# Power_Supply.net
KiCad netlist of a schematic drawn in Altium Designer
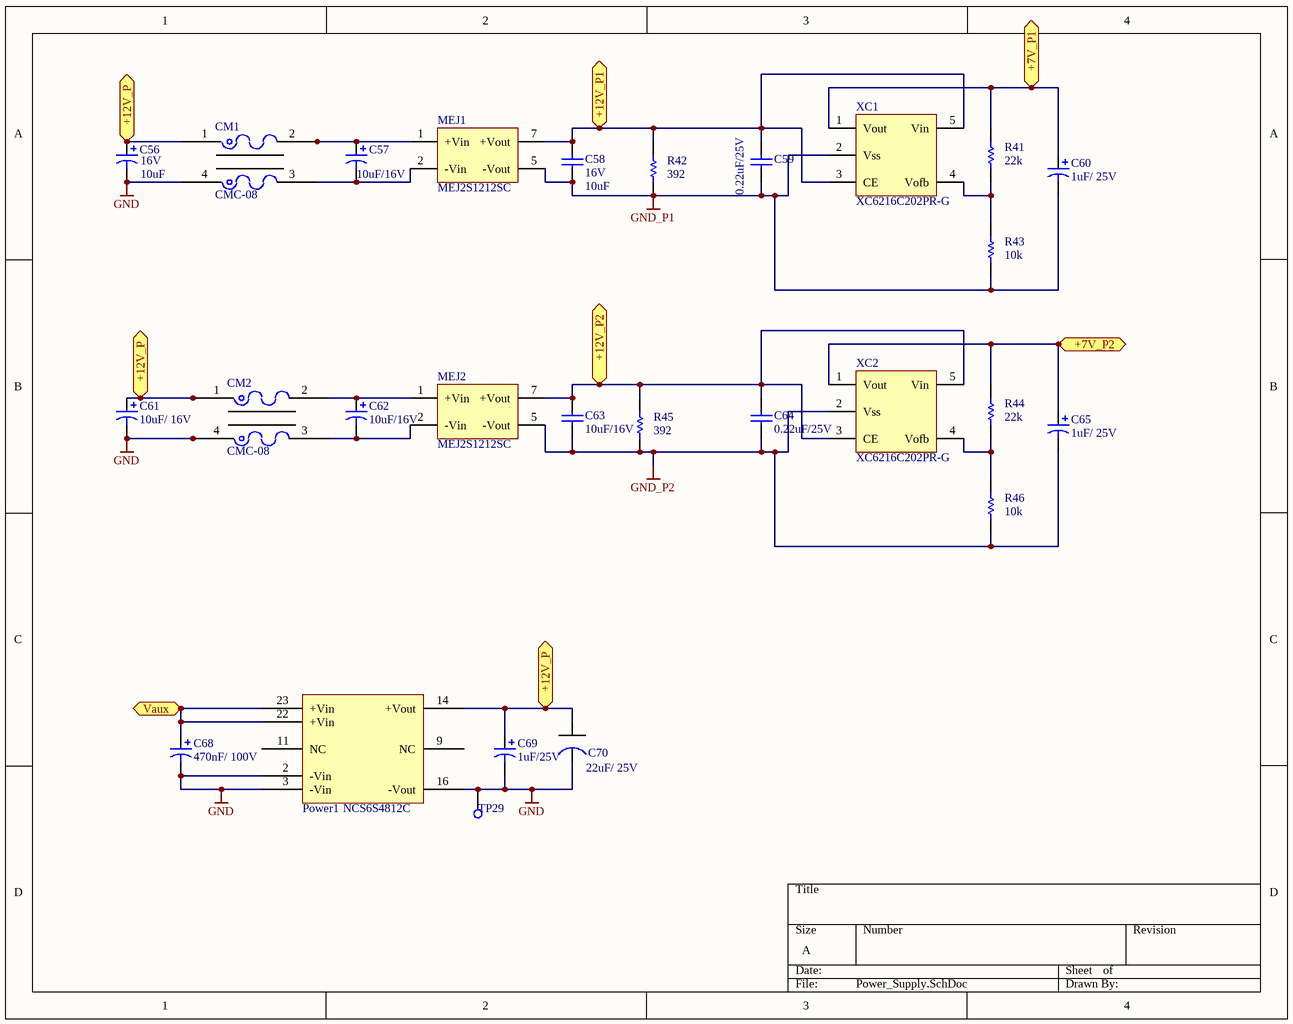
[diagram p0: Power_Supply.SchDoc]

(export (version "E")
  (design (tool "Eeschema 10.0.6"))
  (components
    (comp (ref "C56")
      (value "16V")
      (footprint "1812")
      (description "Polarized Capacitor (Surface Mount)")
      (fields (field (name "ALTIUM_VALUE") "10uF") (field (name "PUBLISHER") "Altium Limited"))
      (libsource (lib "Miscellaneous Devices") (part "Cap Pol3"))
    )
    (comp (ref "C57")
      (value "10uF/16V")
      (footprint "1812")
      (description "Polarized Capacitor (Surface Mount)")
      (fields (field (name "Comment") "Cap Pol3") (field (name "PUBLISHER") "Altium Limited"))
      (libsource (lib "Miscellaneous Devices") (part "Cap Pol3"))
    )
    (comp (ref "C58")
      (value "16V")
      (footprint "C1206")
      (description "Capacitor (Semiconductor SIM Model)")
      (fields (field (name "ALTIUM_VALUE") "10uF") (field (name "PUBLISHER") "Altium Limited"))
      (libsource (lib "Miscellaneous Devices") (part "Cap Semi"))
    )
    (comp (ref "C59")
      (value "0.22uF/25V")
      (footprint "C1206")
      (description "Capacitor (Semiconductor SIM Model)")
      (fields (field (name "Comment") "Cap Semi") (field (name "PUBLISHER") "Altium Limited"))
      (libsource (lib "Miscellaneous Devices") (part "Cap Semi"))
    )
    (comp (ref "C60")
      (value "1uF/ 25V")
      (footprint "C0805")
      (description "Polarized Capacitor (Surface Mount)")
      (fields (field (name "Comment") "Cap Pol3") (field (name "PUBLISHER") "Altium Limited"))
      (libsource (lib "Miscellaneous Devices") (part "Cap Pol3"))
    )
    (comp (ref "C61")
      (value "10uF/ 16V")
      (footprint "1812")
      (description "Polarized Capacitor (Surface Mount)")
      (fields (field (name "Comment") "Cap Pol3") (field (name "PUBLISHER") "Altium Limited"))
      (libsource (lib "Miscellaneous Devices") (part "Cap Pol3"))
    )
    (comp (ref "C62")
      (value "10uF/16V")
      (footprint "1812")
      (description "Polarized Capacitor (Surface Mount)")
      (fields (field (name "Comment") "Cap Pol3") (field (name "PUBLISHER") "Altium Limited"))
      (libsource (lib "Miscellaneous Devices") (part "Cap Pol3"))
    )
    (comp (ref "C63")
      (value "10uF/16V")
      (footprint "C1206")
      (description "Capacitor (Semiconductor SIM Model)")
      (fields (field (name "Comment") "Cap Semi") (field (name "PUBLISHER") "Altium Limited"))
      (libsource (lib "Miscellaneous Devices") (part "Cap Semi"))
    )
    (comp (ref "C64")
      (value "0.22uF/25V")
      (footprint "C1206")
      (description "Capacitor (Semiconductor SIM Model)")
      (fields (field (name "Comment") "Cap Semi") (field (name "PUBLISHER") "Altium Limited"))
      (libsource (lib "Miscellaneous Devices") (part "Cap Semi"))
    )
    (comp (ref "C65")
      (value "1uF/ 25V")
      (footprint "C0805")
      (description "Polarized Capacitor (Surface Mount)")
      (fields (field (name "Comment") "Cap Pol3") (field (name "PUBLISHER") "Altium Limited"))
      (libsource (lib "Miscellaneous Devices") (part "Cap Pol3"))
    )
    (comp (ref "C68")
      (value "470nF/ 100V")
      (footprint "C0805")
      (description "Polarized Capacitor (Surface Mount)")
      (fields (field (name "Comment") "Cap Pol3") (field (name "PUBLISHER") "Altium Limited"))
      (libsource (lib "Miscellaneous Devices") (part "Cap Pol3"))
    )
    (comp (ref "C69")
      (value "1uF/25V")
      (footprint "C0805")
      (description "Polarized Capacitor (Surface Mount)")
      (fields (field (name "Comment") "Cap Pol3") (field (name "PUBLISHER") "Altium Limited"))
      (libsource (lib "Miscellaneous Devices") (part "Cap Pol3"))
    )
    (comp (ref "C70")
      (value "22uF")
      (footprint "Cap_tantalum")
      (fields (field (name "ALTIUM_UNNAMED_1") "22uF/ 25V"))
      (libsource (lib "Schlib1") (part "Cap_tantalum"))
    )
    (comp (ref "CM1")
      (value "CMC-08")
      (footprint "CMC-08")
      (description "Common mode choke")
      (libsource (lib "lib_ankit") (part "CMC-08"))
    )
    (comp (ref "CM2")
      (value "CMC-08")
      (footprint "CMC-08")
      (description "Common mode choke")
      (libsource (lib "lib_ankit") (part "CMC-08"))
    )
    (comp (ref "MEJ1")
      (value "MEJ2S1212SC")
      (footprint "MEJ2")
      (libsource (lib "Gan_cuk converter") (part "Power supply2"))
    )
    (comp (ref "MEJ2")
      (value "MEJ2S1212SC")
      (footprint "MEJ2")
      (libsource (lib "Gan_cuk converter") (part "Power supply2"))
    )
    (comp (ref "Power1")
      (value "NCS6S4812C")
      (footprint "Power_main")
      (libsource (lib "Schlib1") (part "Power_main"))
    )
    (comp (ref "R41")
      (value "res_smd")
      (footprint "res_smd")
      (description "smd_res")
      (fields (field (name "ALTIUM_UNNAMED_1") "22k"))
      (libsource (lib "Schlib1") (part "res_smd"))
    )
    (comp (ref "R42")
      (value "res_smd")
      (footprint "res_smd")
      (description "smd_res")
      (fields (field (name "ALTIUM_UNNAMED_1") "392"))
      (libsource (lib "Schlib1") (part "res_smd"))
    )
    (comp (ref "R43")
      (value "res_smd")
      (footprint "res_smd")
      (description "smd_res")
      (fields (field (name "ALTIUM_UNNAMED_1") "10k"))
      (libsource (lib "Schlib1") (part "res_smd"))
    )
    (comp (ref "R44")
      (value "res_smd")
      (footprint "res_smd")
      (description "smd_res")
      (fields (field (name "ALTIUM_UNNAMED_1") "22k"))
      (libsource (lib "Schlib1") (part "res_smd"))
    )
    (comp (ref "R45")
      (value "res_smd")
      (footprint "res_smd")
      (description "smd_res")
      (fields (field (name "ALTIUM_UNNAMED_1") "392"))
      (libsource (lib "Schlib1") (part "res_smd"))
    )
    (comp (ref "R46")
      (value "res_smd")
      (footprint "res_smd")
      (description "smd_res")
      (fields (field (name "ALTIUM_UNNAMED_1") "10k"))
      (libsource (lib "Schlib1") (part "res_smd"))
    )
    (comp (ref "TP29")
      (value "Test Point")
      (footprint "Test Point")
      (libsource (lib "Gan_cuk converter") (part "Test Point"))
    )
    (comp (ref "XC1")
      (value "XC6216C202PR-G")
      (footprint "SOT-89-5")
      (libsource (lib "Gan_cuk converter") (part "power supply"))
    )
    (comp (ref "XC2")
      (value "XC6216C202PR-G")
      (footprint "SOT-89-5")
      (libsource (lib "Gan_cuk converter") (part "power supply"))
    )
  )
  (nets
    (net (code "1") (name "/+7V_P1") (class "Default")
      (node (ref "C60") (pin "1") (pinfunction "1_1") (pintype "passive"))
      (node (ref "R41") (pin "1") (pintype "passive"))
      (node (ref "XC1") (pin "1") (pinfunction "Vout_1") (pintype "passive"))
    )
    (net (code "2") (name "/+7V_P2") (class "Default")
      (node (ref "C65") (pin "1") (pinfunction "1_1") (pintype "passive"))
      (node (ref "R44") (pin "1") (pintype "passive"))
      (node (ref "XC2") (pin "1") (pinfunction "Vout_1") (pintype "passive"))
    )
    (net (code "3") (name "/+12V_P") (class "Default")
      (node (ref "C56") (pin "1") (pinfunction "1_1") (pintype "passive"))
      (node (ref "C61") (pin "1") (pinfunction "1_1") (pintype "passive"))
      (node (ref "C69") (pin "1") (pinfunction "1_1") (pintype "passive"))
      (node (ref "C70") (pin "1") (pintype "passive"))
      (node (ref "CM1") (pin "1") (pinfunction "1_1") (pintype "passive"))
      (node (ref "CM2") (pin "1") (pinfunction "1_1") (pintype "passive"))
      (node (ref "Power1") (pin "14") (pinfunction "+Vout_14") (pintype "passive"))
    )
    (net (code "4") (name "/+12V_P1") (class "Default")
      (node (ref "C58") (pin "2") (pinfunction "2_2") (pintype "passive"))
      (node (ref "C59") (pin "2") (pinfunction "2_2") (pintype "passive"))
      (node (ref "MEJ1") (pin "7") (pinfunction "+Vout_7") (pintype "passive"))
      (node (ref "R42") (pin "1") (pintype "passive"))
      (node (ref "XC1") (pin "3") (pinfunction "CE_3") (pintype "passive"))
      (node (ref "XC1") (pin "5") (pinfunction "Vin_5") (pintype "passive"))
    )
    (net (code "5") (name "/+12V_P2") (class "Default")
      (node (ref "C63") (pin "2") (pinfunction "2_2") (pintype "passive"))
      (node (ref "C64") (pin "2") (pinfunction "2_2") (pintype "passive"))
      (node (ref "MEJ2") (pin "7") (pinfunction "+Vout_7") (pintype "passive"))
      (node (ref "R45") (pin "1") (pintype "passive"))
      (node (ref "XC2") (pin "3") (pinfunction "CE_3") (pintype "passive"))
      (node (ref "XC2") (pin "5") (pinfunction "Vin_5") (pintype "passive"))
    )
    (net (code "6") (name "/Vaux") (class "Default")
      (node (ref "C68") (pin "1") (pinfunction "1_1") (pintype "passive"))
      (node (ref "Power1") (pin "22") (pinfunction "+Vin_22") (pintype "passive"))
      (node (ref "Power1") (pin "23") (pinfunction "+Vin_23") (pintype "passive"))
    )
    (net (code "7") (name "GND") (class "Default")
      (node (ref "C56") (pin "2") (pinfunction "2_2") (pintype "passive"))
      (node (ref "C61") (pin "2") (pinfunction "2_2") (pintype "passive"))
      (node (ref "C68") (pin "2") (pinfunction "2_2") (pintype "passive"))
      (node (ref "C69") (pin "2") (pinfunction "2_2") (pintype "passive"))
      (node (ref "C70") (pin "2") (pintype "passive"))
      (node (ref "CM1") (pin "4") (pinfunction "4_4") (pintype "passive"))
      (node (ref "CM2") (pin "4") (pinfunction "4_4") (pintype "passive"))
      (node (ref "Power1") (pin "16") (pinfunction "-Vout_16") (pintype "passive"))
      (node (ref "Power1") (pin "2") (pinfunction "-Vin_2") (pintype "passive"))
      (node (ref "Power1") (pin "3") (pinfunction "-Vin_3") (pintype "passive"))
      (node (ref "TP29") (pin "1") (pinfunction "TP?_1") (pintype "passive"))
    )
    (net (code "8") (name "GND_P1") (class "Default")
      (node (ref "C58") (pin "1") (pinfunction "1_1") (pintype "passive"))
      (node (ref "C59") (pin "1") (pinfunction "1_1") (pintype "passive"))
      (node (ref "C60") (pin "2") (pinfunction "2_2") (pintype "passive"))
      (node (ref "MEJ1") (pin "5") (pinfunction "-Vout_5") (pintype "passive"))
      (node (ref "R42") (pin "2") (pintype "passive"))
      (node (ref "R43") (pin "2") (pintype "passive"))
      (node (ref "XC1") (pin "2") (pinfunction "Vss_2") (pintype "passive"))
    )
    (net (code "9") (name "GND_P2") (class "Default")
      (node (ref "C63") (pin "1") (pinfunction "1_1") (pintype "passive"))
      (node (ref "C64") (pin "1") (pinfunction "1_1") (pintype "passive"))
      (node (ref "C65") (pin "2") (pinfunction "2_2") (pintype "passive"))
      (node (ref "MEJ2") (pin "5") (pinfunction "-Vout_5") (pintype "passive"))
      (node (ref "R45") (pin "2") (pintype "passive"))
      (node (ref "R46") (pin "2") (pintype "passive"))
      (node (ref "XC2") (pin "2") (pinfunction "Vss_2") (pintype "passive"))
    )
    (net (code "10") (name "Net-(MEJ1-+Vin)") (class "Default")
      (node (ref "C57") (pin "1") (pinfunction "1_1") (pintype "passive"))
      (node (ref "CM1") (pin "2") (pinfunction "2_2") (pintype "passive"))
      (node (ref "MEJ1") (pin "1") (pinfunction "+Vin_1") (pintype "passive"))
    )
    (net (code "11") (name "Net-(MEJ1--Vin)") (class "Default")
      (node (ref "C57") (pin "2") (pinfunction "2_2") (pintype "passive"))
      (node (ref "CM1") (pin "3") (pinfunction "3_3") (pintype "passive"))
      (node (ref "MEJ1") (pin "2") (pinfunction "-Vin_2") (pintype "passive"))
    )
    (net (code "12") (name "Net-(MEJ2-+Vin)") (class "Default")
      (node (ref "C62") (pin "1") (pinfunction "1_1") (pintype "passive"))
      (node (ref "CM2") (pin "2") (pinfunction "2_2") (pintype "passive"))
      (node (ref "MEJ2") (pin "1") (pinfunction "+Vin_1") (pintype "passive"))
    )
    (net (code "13") (name "Net-(MEJ2--Vin)") (class "Default")
      (node (ref "C62") (pin "2") (pinfunction "2_2") (pintype "passive"))
      (node (ref "CM2") (pin "3") (pinfunction "3_3") (pintype "passive"))
      (node (ref "MEJ2") (pin "2") (pinfunction "-Vin_2") (pintype "passive"))
    )
    (net (code "14") (name "Net-(XC1-Vofb)") (class "Default")
      (node (ref "R41") (pin "2") (pintype "passive"))
      (node (ref "R43") (pin "1") (pintype "passive"))
      (node (ref "XC1") (pin "4") (pinfunction "Vofb_4") (pintype "passive"))
    )
    (net (code "15") (name "Net-(XC2-Vofb)") (class "Default")
      (node (ref "R44") (pin "2") (pintype "passive"))
      (node (ref "R46") (pin "1") (pintype "passive"))
      (node (ref "XC2") (pin "4") (pinfunction "Vofb_4") (pintype "passive"))
    )
    (net (code "16") (name "unconnected-(Power1-NC-Pad9)") (class "Default")
      (node (ref "Power1") (pin "9") (pinfunction "NC_9") (pintype "passive"))
    )
    (net (code "17") (name "unconnected-(Power1-NC-Pad11)") (class "Default")
      (node (ref "Power1") (pin "11") (pinfunction "NC_11") (pintype "passive"))
    )
  )
)
